# ADS7128.net
KiCad netlist of a schematic drawn in EAGLE
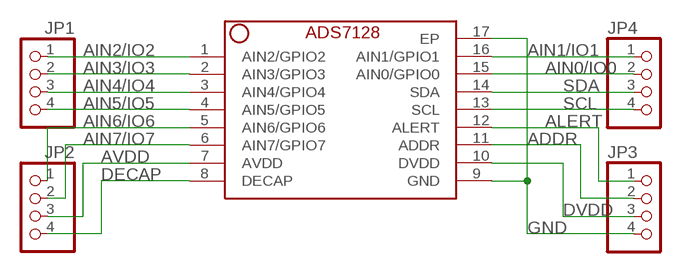
[diagram p0: schematic, sheet 1]

(export (version "E")
  (design (tool "Eeschema 10.0.6"))
  (components
    (comp (ref "JP1")
      (value "PINHD-1X4")
      (footprint "eagle-import:1X04")
      (libsource (lib "eagle-import") (part "PINHD-1X4"))
    )
    (comp (ref "JP2")
      (value "PINHD-1X4")
      (footprint "eagle-import:1X04")
      (libsource (lib "eagle-import") (part "PINHD-1X4"))
    )
    (comp (ref "JP3")
      (value "PINHD-1X4")
      (footprint "eagle-import:1X04")
      (libsource (lib "eagle-import") (part "PINHD-1X4"))
    )
    (comp (ref "JP4")
      (value "PINHD-1X4")
      (footprint "eagle-import:1X04")
      (libsource (lib "eagle-import") (part "PINHD-1X4"))
    )
    (comp (ref "U$1")
      (value "ADS7128")
      (footprint "eagle-import:QFN50P300X300X80-17N")
      (libsource (lib "eagle-import") (part "ADS7128"))
    )
  )
  (nets
    (net (code "1") (name "/ADDR") (class "Default")
      (node (ref "JP3") (pin "2") (pinfunction "2_2") (pintype "passive"))
      (node (ref "U$1") (pin "11") (pinfunction "ADDR_11") (pintype "bidirectional"))
    )
    (net (code "2") (name "/AIN0{slash}IO0") (class "Default")
      (node (ref "JP4") (pin "2") (pinfunction "2_2") (pintype "passive"))
      (node (ref "U$1") (pin "15") (pinfunction "AIN0/GPIO0_15") (pintype "bidirectional"))
    )
    (net (code "3") (name "/AIN1{slash}IO1") (class "Default")
      (node (ref "JP4") (pin "1") (pinfunction "1_1") (pintype "passive"))
      (node (ref "U$1") (pin "16") (pinfunction "AIN1/GPIO1_16") (pintype "bidirectional"))
    )
    (net (code "4") (name "/AIN2{slash}IO2") (class "Default")
      (node (ref "JP1") (pin "1") (pinfunction "1_1") (pintype "passive"))
      (node (ref "U$1") (pin "1") (pinfunction "AIN2/GPIO2_1") (pintype "bidirectional"))
    )
    (net (code "5") (name "/AIN3{slash}IO3") (class "Default")
      (node (ref "JP1") (pin "2") (pinfunction "2_2") (pintype "passive"))
      (node (ref "U$1") (pin "2") (pinfunction "AIN3/GPIO3_2") (pintype "bidirectional"))
    )
    (net (code "6") (name "/AIN4{slash}IO4") (class "Default")
      (node (ref "JP1") (pin "3") (pinfunction "3_3") (pintype "passive"))
      (node (ref "U$1") (pin "3") (pinfunction "AIN4/GPIO4_3") (pintype "bidirectional"))
    )
    (net (code "7") (name "/AIN5{slash}IO5") (class "Default")
      (node (ref "JP1") (pin "4") (pinfunction "4_4") (pintype "passive"))
      (node (ref "U$1") (pin "4") (pinfunction "AIN5/GPIO5_4") (pintype "bidirectional"))
    )
    (net (code "8") (name "/AIN6{slash}IO6") (class "Default")
      (node (ref "JP2") (pin "1") (pinfunction "1_1") (pintype "passive"))
      (node (ref "U$1") (pin "5") (pinfunction "AIN6/GPIO6_5") (pintype "bidirectional"))
    )
    (net (code "9") (name "/AIN7{slash}IO7") (class "Default")
      (node (ref "JP2") (pin "2") (pinfunction "2_2") (pintype "passive"))
      (node (ref "U$1") (pin "6") (pinfunction "AIN7/GPIO7_6") (pintype "bidirectional"))
    )
    (net (code "10") (name "/ALERT") (class "Default")
      (node (ref "JP3") (pin "1") (pinfunction "1_1") (pintype "passive"))
      (node (ref "U$1") (pin "12") (pinfunction "ALERT_12") (pintype "bidirectional"))
    )
    (net (code "11") (name "/AVDD") (class "Default")
      (node (ref "JP2") (pin "3") (pinfunction "3_3") (pintype "passive"))
      (node (ref "U$1") (pin "7") (pinfunction "AVDD_7") (pintype "bidirectional"))
    )
    (net (code "12") (name "/DECAP") (class "Default")
      (node (ref "JP2") (pin "4") (pinfunction "4_4") (pintype "passive"))
      (node (ref "U$1") (pin "8") (pinfunction "DECAP_8") (pintype "bidirectional"))
    )
    (net (code "13") (name "/DVDD") (class "Default")
      (node (ref "JP3") (pin "3") (pinfunction "3_3") (pintype "passive"))
      (node (ref "U$1") (pin "10") (pinfunction "DVDD_10") (pintype "bidirectional"))
    )
    (net (code "14") (name "/GND") (class "Default")
      (node (ref "JP3") (pin "4") (pinfunction "4_4") (pintype "passive"))
      (node (ref "U$1") (pin "17") (pinfunction "EP_17") (pintype "bidirectional"))
      (node (ref "U$1") (pin "9") (pinfunction "GND_9") (pintype "bidirectional"))
    )
    (net (code "15") (name "/SCL") (class "Default")
      (node (ref "JP4") (pin "4") (pinfunction "4_4") (pintype "passive"))
      (node (ref "U$1") (pin "13") (pinfunction "SCL_13") (pintype "bidirectional"))
    )
    (net (code "16") (name "/SDA") (class "Default")
      (node (ref "JP4") (pin "3") (pinfunction "3_3") (pintype "passive"))
      (node (ref "U$1") (pin "14") (pinfunction "SDA_14") (pintype "bidirectional"))
    )
  )
)
